# design.net
KiCad netlist of a schematic drawn in Altium Designer
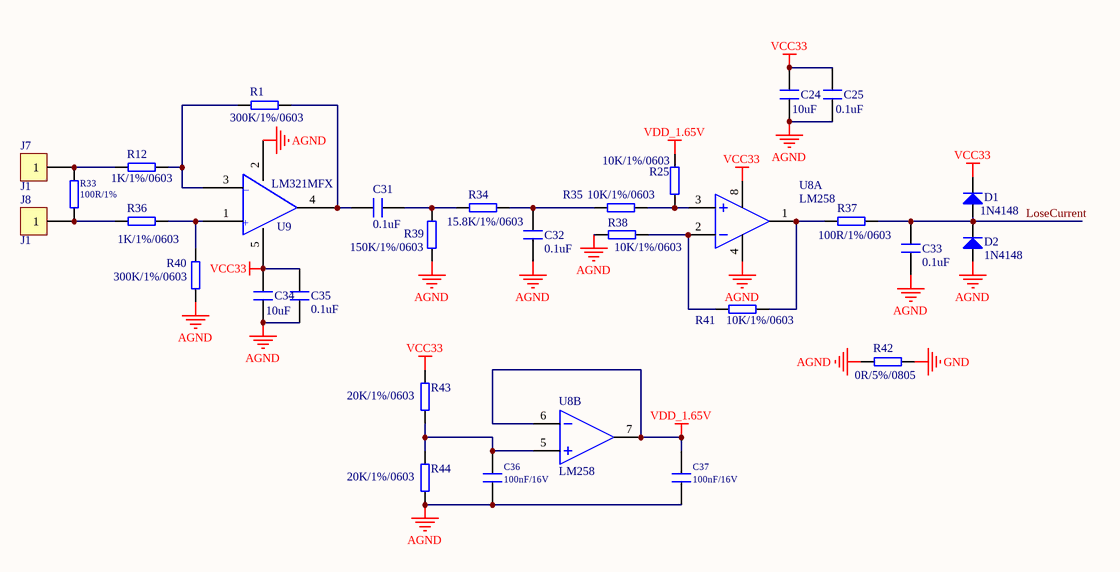
[diagram p0: 漏电流检测.SchDoc]

(export (version "E")
  (design (tool "Eeschema 10.0.6"))
  (components
    (comp (ref "C24") (value "10uF") (footprint "0603R") (libsource (lib "ES_Schematic") (part "CAP")))
    (comp (ref "C25") (value "0.1uF") (footprint "0603R") (libsource (lib "ES_Schematic") (part "CAP")))
    (comp (ref "C31") (value "0.1uF") (footprint "0603R") (libsource (lib "ES_Schematic") (part "CAP")))
    (comp (ref "C32") (value "0.1uF") (footprint "0603R") (libsource (lib "ES_Schematic") (part "CAP")))
    (comp (ref "C33") (value "0.1uF") (footprint "0603R") (libsource (lib "ES_Schematic") (part "CAP")))
    (comp (ref "C34") (value "10uF") (footprint "0603R") (libsource (lib "ES_Schematic") (part "CAP")))
    (comp (ref "C35") (value "0.1uF") (footprint "0603R") (libsource (lib "ES_Schematic") (part "CAP")))
    (comp (ref "C36") (value "100nF/16V") (footprint "0603R") (libsource (lib "ES_Schematic") (part "CAP")))
    (comp (ref "C37") (value "100nF/16V") (footprint "0603R") (libsource (lib "ES_Schematic") (part "CAP")))
    (comp (ref "D1") (value "1N4148") (footprint "1206D") (libsource (lib "ES_Schematic") (part "DIODE")))
    (comp (ref "D2") (value "1N4148") (footprint "1206D") (libsource (lib "ES_Schematic") (part "DIODE")))
    (comp (ref "J7") (value "J1") (footprint "贴片焊盘V1（3*2椭圆）") (libsource (lib "ES_Schematic") (part "J1")))
    (comp (ref "J8") (value "J1") (footprint "贴片焊盘V1（3*2椭圆）") (libsource (lib "ES_Schematic") (part "J1")))
    (comp (ref "R1") (value "300K/1%/0603") (footprint "0603r") (libsource (lib "ES_Schematic") (part "RES")))
    (comp (ref "R12") (value "1K/1%/0603") (footprint "0603r") (libsource (lib "ES_Schematic") (part "RES")))
    (comp (ref "R25") (value "10K/1%/0603") (footprint "0603r") (libsource (lib "ES_Schematic") (part "RES")))
    (comp (ref "R33") (value "100R/1%") (footprint "0805R") (libsource (lib "ES_Schematic") (part "RES")))
    (comp (ref "R34")
      (value "15.8K/1%/0603")
      (footprint "0603r")
      (libsource (lib "ES_Schematic") (part "RES"))
    )
    (comp (ref "R35") (value "10K/1%/0603") (footprint "0603r") (libsource (lib "ES_Schematic") (part "RES")))
    (comp (ref "R36") (value "1K/1%/0603") (footprint "0603r") (libsource (lib "ES_Schematic") (part "RES")))
    (comp (ref "R37")
      (value "100R/1%/0603")
      (footprint "0603r")
      (libsource (lib "ES_Schematic") (part "RES"))
    )
    (comp (ref "R38") (value "10K/1%/0603") (footprint "0603r") (libsource (lib "ES_Schematic") (part "RES")))
    (comp (ref "R39")
      (value "150K/1%/0603")
      (footprint "0603r")
      (libsource (lib "ES_Schematic") (part "RES"))
    )
    (comp (ref "R40")
      (value "300K/1%/0603")
      (footprint "0603r")
      (libsource (lib "ES_Schematic") (part "RES"))
    )
    (comp (ref "R41") (value "10K/1%/0603") (footprint "0603r") (libsource (lib "ES_Schematic") (part "RES")))
    (comp (ref "R42") (value "0R/5%/0805") (footprint "0805R") (libsource (lib "ES_Schematic") (part "RES")))
    (comp (ref "R43") (value "20K/1%/0603") (footprint "0603r") (libsource (lib "ES_Schematic") (part "RES")))
    (comp (ref "R44") (value "20K/1%/0603") (footprint "0603r") (libsource (lib "ES_Schematic") (part "RES")))
    (comp (ref "U8") (value "LM258") (footprint "SO8") (libsource (lib "sangjian") (part "LM358")))
    (comp (ref "U9")
      (value "LM321MFX")
      (footprint "SOT-23-5")
      (libsource (lib "ES_Schematic") (part "LM321MFX"))
    )
  )
  (nets
    (net (code "1") (name "/LoseCurrent") (class "Default")
      (node (ref "C33") (pin "1") (pinfunction "1_1") (pintype "passive"))
      (node (ref "D1") (pin "2") (pinfunction "A_2") (pintype "passive"))
      (node (ref "D2") (pin "1") (pinfunction "K_1") (pintype "passive"))
      (node (ref "R37") (pin "1") (pinfunction "1_1") (pintype "passive"))
    )
    (net (code "2") (name "AGND") (class "Default")
      (node (ref "C24") (pin "1") (pinfunction "1_1") (pintype "passive"))
      (node (ref "C25") (pin "1") (pinfunction "1_1") (pintype "passive"))
      (node (ref "C32") (pin "2") (pinfunction "2_2") (pintype "passive"))
      (node (ref "C33") (pin "2") (pinfunction "2_2") (pintype "passive"))
      (node (ref "C34") (pin "1") (pinfunction "1_1") (pintype "passive"))
      (node (ref "C35") (pin "1") (pinfunction "1_1") (pintype "passive"))
      (node (ref "C36") (pin "2") (pinfunction "2_2") (pintype "passive"))
      (node (ref "C37") (pin "2") (pinfunction "2_2") (pintype "passive"))
      (node (ref "D2") (pin "2") (pinfunction "A_2") (pintype "passive"))
      (node (ref "R38") (pin "2") (pinfunction "2_2") (pintype "passive"))
      (node (ref "R39") (pin "1") (pinfunction "1_1") (pintype "passive"))
      (node (ref "R40") (pin "1") (pinfunction "1_1") (pintype "passive"))
      (node (ref "R42") (pin "2") (pinfunction "2_2") (pintype "passive"))
      (node (ref "R44") (pin "2") (pinfunction "2_2") (pintype "passive"))
      (node (ref "U8") (pin "4") (pinfunction "4_4") (pintype "passive"))
      (node (ref "U9") (pin "2") (pintype "passive"))
    )
    (net (code "3") (name "GND") (class "Default")
      (node (ref "R42") (pin "1") (pinfunction "1_1") (pintype "passive"))
    )
    (net (code "4") (name "Net-(C31-Pad1)") (class "Default")
      (node (ref "C31") (pin "1") (pinfunction "1_1") (pintype "passive"))
      (node (ref "R34") (pin "2") (pinfunction "2_2") (pintype "passive"))
      (node (ref "R39") (pin "2") (pinfunction "2_2") (pintype "passive"))
    )
    (net (code "5") (name "Net-(C31-Pad2)") (class "Default")
      (node (ref "C31") (pin "2") (pinfunction "2_2") (pintype "passive"))
      (node (ref "R1") (pin "1") (pinfunction "1_1") (pintype "passive"))
      (node (ref "U9") (pin "4") (pintype "passive"))
    )
    (net (code "6") (name "Net-(C32-Pad1)") (class "Default")
      (node (ref "C32") (pin "1") (pinfunction "1_1") (pintype "passive"))
      (node (ref "R34") (pin "1") (pinfunction "1_1") (pintype "passive"))
      (node (ref "R35") (pin "2") (pinfunction "2_2") (pintype "passive"))
    )
    (net (code "7") (name "Net-(C36-Pad1)") (class "Default")
      (node (ref "C36") (pin "1") (pinfunction "1_1") (pintype "passive"))
      (node (ref "R43") (pin "2") (pinfunction "2_2") (pintype "passive"))
      (node (ref "R44") (pin "1") (pinfunction "1_1") (pintype "passive"))
      (node (ref "U8") (pin "5") (pinfunction "5_5") (pintype "passive"))
    )
    (net (code "8") (name "Net-(J7-Pad1)") (class "Default")
      (node (ref "J7") (pin "1") (pinfunction "1_1") (pintype "passive"))
      (node (ref "R12") (pin "1") (pinfunction "1_1") (pintype "passive"))
      (node (ref "R33") (pin "2") (pinfunction "2_2") (pintype "passive"))
    )
    (net (code "9") (name "Net-(J8-Pad1)") (class "Default")
      (node (ref "J8") (pin "1") (pinfunction "1_1") (pintype "passive"))
      (node (ref "R33") (pin "1") (pinfunction "1_1") (pintype "passive"))
      (node (ref "R36") (pin "2") (pinfunction "2_2") (pintype "passive"))
    )
    (net (code "10") (name "Net-(R1-Pad2)") (class "Default")
      (node (ref "R1") (pin "2") (pinfunction "2_2") (pintype "passive"))
      (node (ref "R12") (pin "2") (pinfunction "2_2") (pintype "passive"))
      (node (ref "U9") (pin "3") (pintype "passive"))
    )
    (net (code "11") (name "Net-(R25-Pad2)") (class "Default")
      (node (ref "R25") (pin "2") (pinfunction "2_2") (pintype "passive"))
      (node (ref "R35") (pin "1") (pinfunction "1_1") (pintype "passive"))
      (node (ref "U8") (pin "3") (pinfunction "3_3") (pintype "passive"))
    )
    (net (code "12") (name "Net-(R36-Pad1)") (class "Default")
      (node (ref "R36") (pin "1") (pinfunction "1_1") (pintype "passive"))
      (node (ref "R40") (pin "2") (pinfunction "2_2") (pintype "passive"))
      (node (ref "U9") (pin "1") (pintype "passive"))
    )
    (net (code "13") (name "Net-(R37-Pad2)") (class "Default")
      (node (ref "R37") (pin "2") (pinfunction "2_2") (pintype "passive"))
      (node (ref "R41") (pin "1") (pinfunction "1_1") (pintype "passive"))
      (node (ref "U8") (pin "1") (pinfunction "1_1") (pintype "passive"))
    )
    (net (code "14") (name "Net-(R38-Pad1)") (class "Default")
      (node (ref "R38") (pin "1") (pinfunction "1_1") (pintype "passive"))
      (node (ref "R41") (pin "2") (pinfunction "2_2") (pintype "passive"))
      (node (ref "U8") (pin "2") (pinfunction "2_2") (pintype "passive"))
    )
    (net (code "15") (name "VCC33") (class "Default")
      (node (ref "C24") (pin "2") (pinfunction "2_2") (pintype "passive"))
      (node (ref "C25") (pin "2") (pinfunction "2_2") (pintype "passive"))
      (node (ref "C34") (pin "2") (pinfunction "2_2") (pintype "passive"))
      (node (ref "C35") (pin "2") (pinfunction "2_2") (pintype "passive"))
      (node (ref "D1") (pin "1") (pinfunction "K_1") (pintype "passive"))
      (node (ref "R43") (pin "1") (pinfunction "1_1") (pintype "passive"))
      (node (ref "U8") (pin "8") (pinfunction "8_8") (pintype "passive"))
      (node (ref "U9") (pin "5") (pintype "passive"))
    )
    (net (code "16") (name "VDD_1.65V") (class "Default")
      (node (ref "C37") (pin "1") (pinfunction "1_1") (pintype "passive"))
      (node (ref "R25") (pin "1") (pinfunction "1_1") (pintype "passive"))
      (node (ref "U8") (pin "6") (pinfunction "6_6") (pintype "passive"))
      (node (ref "U8") (pin "7") (pinfunction "7_7") (pintype "passive"))
    )
  )
)
